# mipi_deserializer.net
KiCad netlist of a schematic drawn in Altium Designer
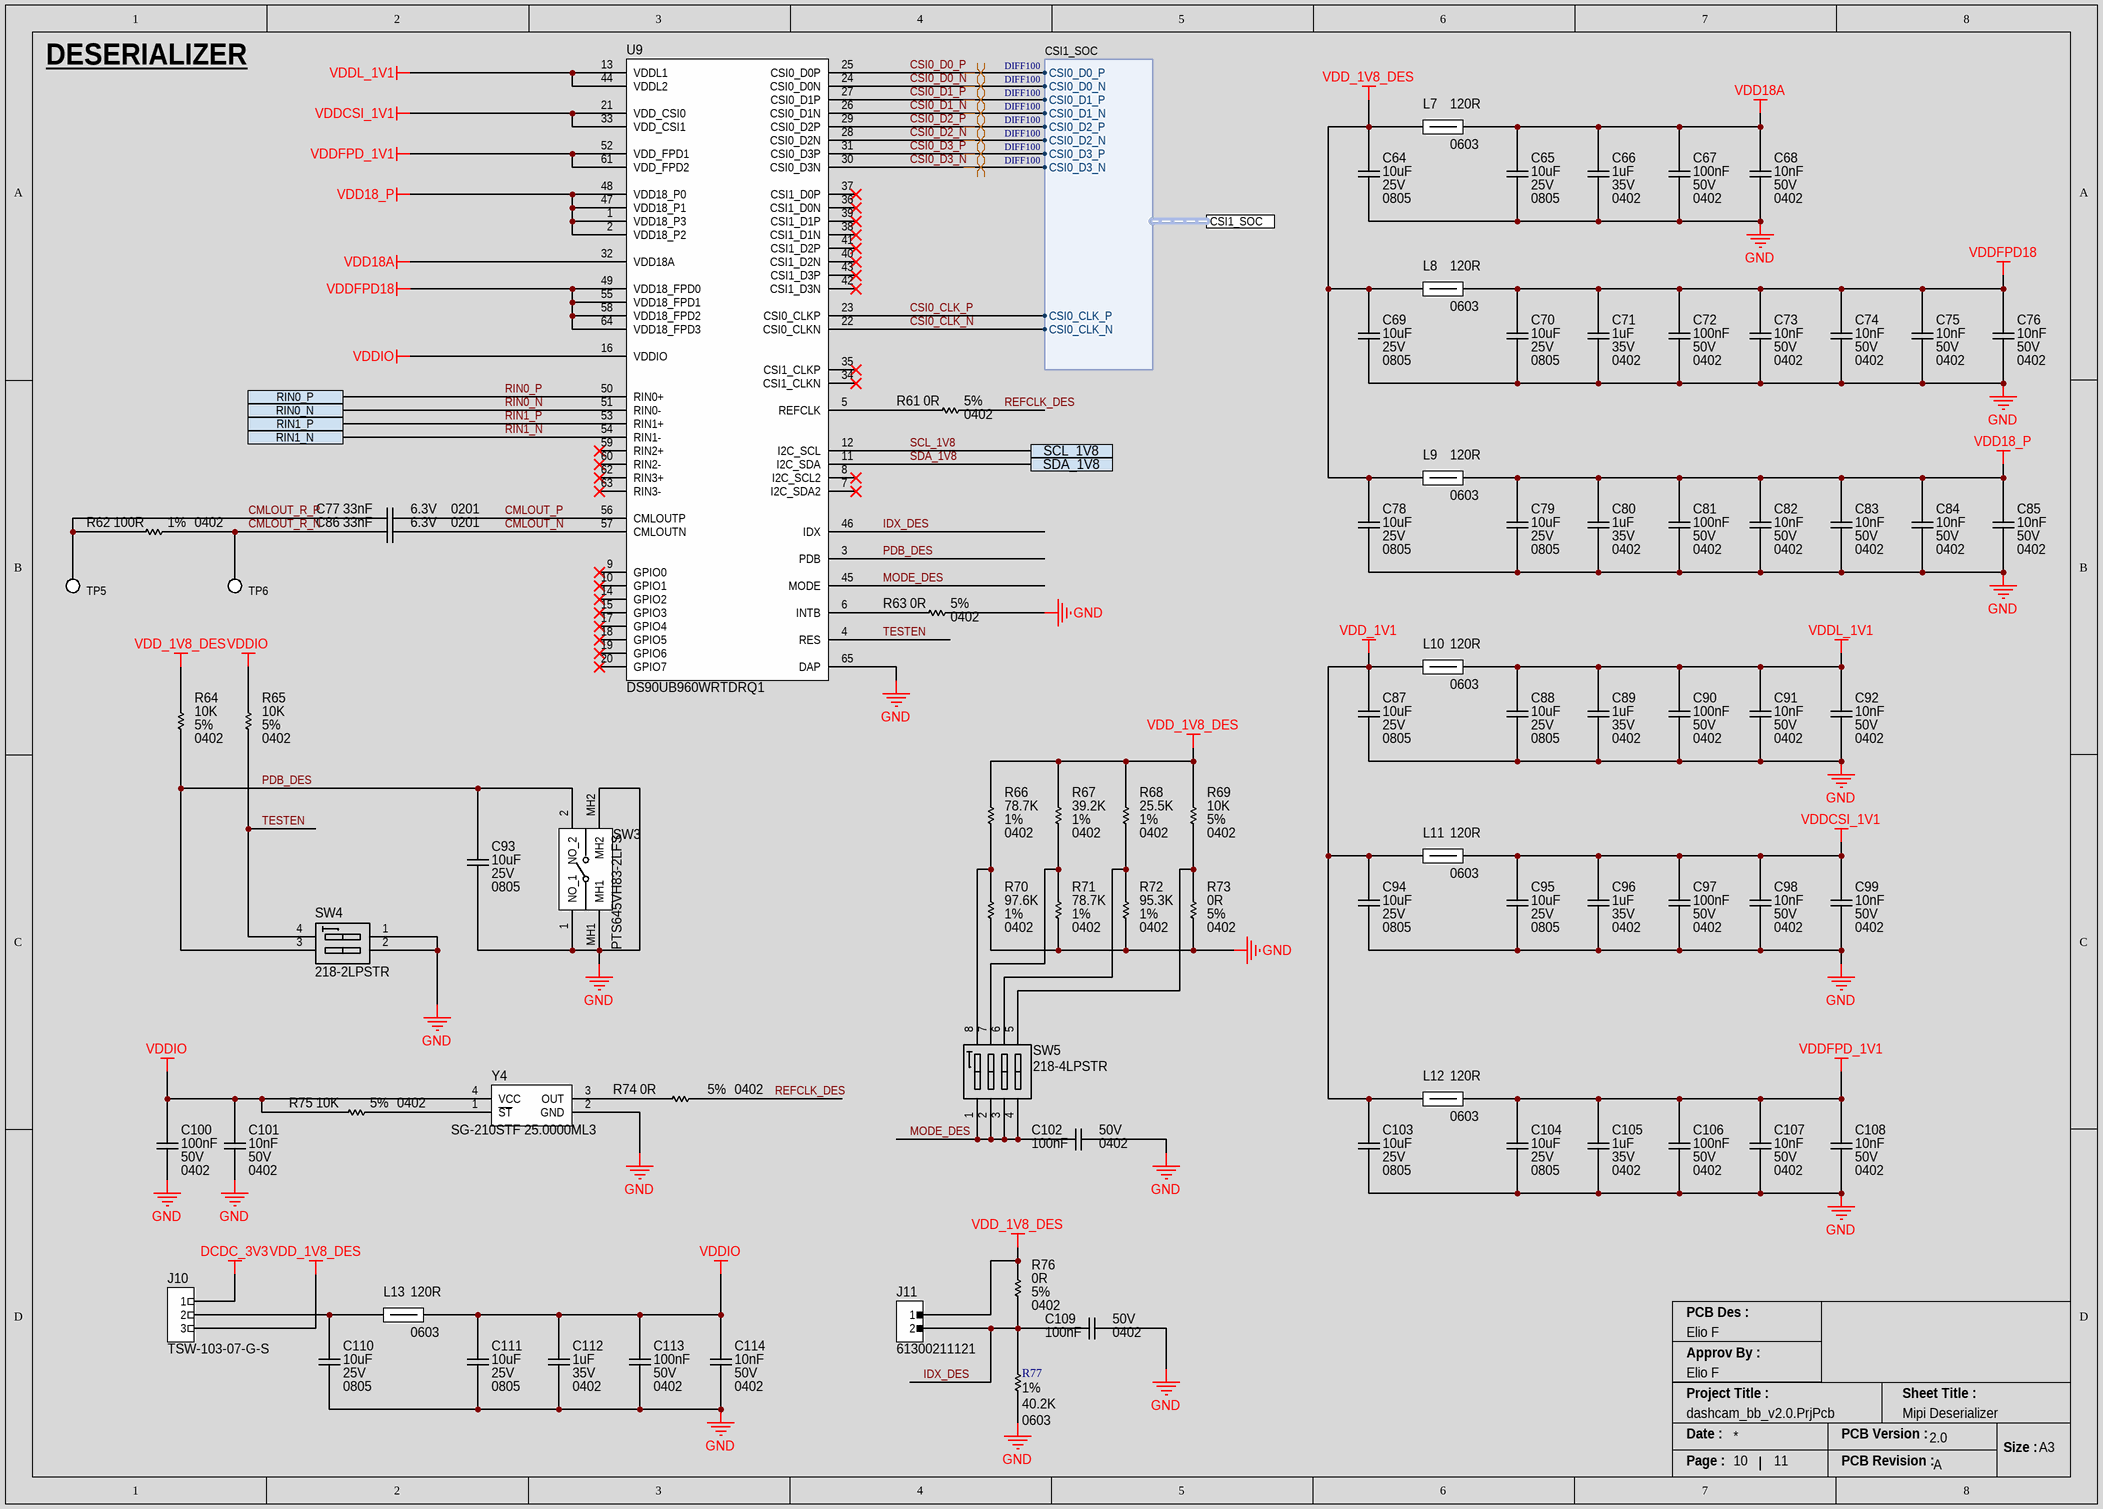
[diagram p0: mipi_deserializer.SchDoc]

(export (version "E")
  (design (tool "Eeschema 10.0.6"))
  (components
    (comp (ref "C64")
      (value "CL21A106KAYNNNE")
      (footprint "CAP_0805_CAPC2012X12N")
      (description "CAP CER 10UF 25V X5R 0805")
      (fields
        (field (name "MANUFACTURER") "Samsung")
        (field (name "TOLERANCE") "10%")
        (field (name "VOLTAGE RATING") "25V")
        (field (name "CAPACITANCE") "10uF")
        (field (name "CASE/PACKAGE") "0805")
      )
      (libsource (lib "Electronic Devices_LIB") (part "CAP_10UF_25V_X5R_0805"))
    )
    (comp (ref "C65")
      (value "CL21A106KAYNNNE")
      (footprint "CAP_0805_CAPC2012X12N")
      (description "CAP CER 10UF 25V X5R 0805")
      (fields
        (field (name "MANUFACTURER") "Samsung")
        (field (name "TOLERANCE") "10%")
        (field (name "VOLTAGE RATING") "25V")
        (field (name "CAPACITANCE") "10uF")
        (field (name "CASE/PACKAGE") "0805")
      )
      (libsource (lib "Electronic Devices_LIB") (part "CAP_10UF_25V_X5R_0805"))
    )
    (comp (ref "C66")
      (value "C1005JB1V105K050BC")
      (footprint "CAP_0402_CAPC1005X05N")
      (description "Cap Ceramic 1uF 35V JB 10% SMD 0402 85°C Punched Paper T/R")
      (fields
        (field (name "MANUFACTURER") "TDK")
        (field (name "TOLERANCE") "10%")
        (field (name "VOLTAGE RATING") "35V")
        (field (name "CAPACITANCE") "1uF")
        (field (name "CASE/PACKAGE") "0402")
      )
      (libsource (lib "Electronic Devices_LIB") (part "CAP_1uF_35V_JB_0402"))
    )
    (comp (ref "C67")
      (value "GRM155R71H104KE14D")
      (footprint "CAP_0402_CAPC1005X05N")
      (description "Multilayer Ceramic Capacitor, 0.1 uF, 16 V, ± 10%, X7R, 0402 [1005 Metric]")
      (fields
        (field (name "MANUFACTURER") "Murata")
        (field (name "TOLERANCE") "10%")
        (field (name "VOLTAGE RATING") "50V")
        (field (name "CAPACITANCE") "100nF")
        (field (name "CASE/PACKAGE") "0402")
      )
      (libsource (lib "Electronic Devices_LIB") (part "CAP_100NF_50V_X7R_0402"))
    )
    (comp (ref "C68")
      (value "GRM155R71H103KA88D")
      (footprint "CAP_0402_CAPC1005X05N")
      (description "Multilayer Ceramic Capacitors MLCC Surface Mount 0402 0.01uF 50 Volts X7R 10%")
      (fields
        (field (name "MANUFACTURER") "Murata")
        (field (name "TOLERANCE") "10%")
        (field (name "VOLTAGE RATING") "50V")
        (field (name "CAPACITANCE") "10nF")
        (field (name "CASE/PACKAGE") "0402")
      )
      (libsource (lib "Electronic Devices_LIB") (part "CAP_10nF_50V_X7R_0402"))
    )
    (comp (ref "C69")
      (value "CL21A106KAYNNNE")
      (footprint "CAP_0805_CAPC2012X12N")
      (description "CAP CER 10UF 25V X5R 0805")
      (fields
        (field (name "MANUFACTURER") "Samsung")
        (field (name "TOLERANCE") "10%")
        (field (name "VOLTAGE RATING") "25V")
        (field (name "CAPACITANCE") "10uF")
        (field (name "CASE/PACKAGE") "0805")
      )
      (libsource (lib "Electronic Devices_LIB") (part "CAP_10UF_25V_X5R_0805"))
    )
    (comp (ref "C70")
      (value "CL21A106KAYNNNE")
      (footprint "CAP_0805_CAPC2012X12N")
      (description "CAP CER 10UF 25V X5R 0805")
      (fields
        (field (name "MANUFACTURER") "Samsung")
        (field (name "TOLERANCE") "10%")
        (field (name "VOLTAGE RATING") "25V")
        (field (name "CAPACITANCE") "10uF")
        (field (name "CASE/PACKAGE") "0805")
      )
      (libsource (lib "Electronic Devices_LIB") (part "CAP_10UF_25V_X5R_0805"))
    )
    (comp (ref "C71")
      (value "C1005JB1V105K050BC")
      (footprint "CAP_0402_CAPC1005X05N")
      (description "Cap Ceramic 1uF 35V JB 10% SMD 0402 85°C Punched Paper T/R")
      (fields
        (field (name "MANUFACTURER") "TDK")
        (field (name "TOLERANCE") "10%")
        (field (name "VOLTAGE RATING") "35V")
        (field (name "CAPACITANCE") "1uF")
        (field (name "CASE/PACKAGE") "0402")
      )
      (libsource (lib "Electronic Devices_LIB") (part "CAP_1uF_35V_JB_0402"))
    )
    (comp (ref "C72")
      (value "GRM155R71H104KE14D")
      (footprint "CAP_0402_CAPC1005X05N")
      (description "Multilayer Ceramic Capacitor, 0.1 uF, 16 V, ± 10%, X7R, 0402 [1005 Metric]")
      (fields
        (field (name "MANUFACTURER") "Murata")
        (field (name "TOLERANCE") "10%")
        (field (name "VOLTAGE RATING") "50V")
        (field (name "CAPACITANCE") "100nF")
        (field (name "CASE/PACKAGE") "0402")
      )
      (libsource (lib "Electronic Devices_LIB") (part "CAP_100NF_50V_X7R_0402"))
    )
    (comp (ref "C73")
      (value "GRM155R71H103KA88D")
      (footprint "CAP_0402_CAPC1005X05N")
      (description "Multilayer Ceramic Capacitors MLCC Surface Mount 0402 0.01uF 50 Volts X7R 10%")
      (fields
        (field (name "MANUFACTURER") "Murata")
        (field (name "TOLERANCE") "10%")
        (field (name "VOLTAGE RATING") "50V")
        (field (name "CAPACITANCE") "10nF")
        (field (name "CASE/PACKAGE") "0402")
      )
      (libsource (lib "Electronic Devices_LIB") (part "CAP_10nF_50V_X7R_0402"))
    )
    (comp (ref "C74")
      (value "GRM155R71H103KA88D")
      (footprint "CAP_0402_CAPC1005X05N")
      (description "Multilayer Ceramic Capacitors MLCC Surface Mount 0402 0.01uF 50 Volts X7R 10%")
      (fields
        (field (name "MANUFACTURER") "Murata")
        (field (name "TOLERANCE") "10%")
        (field (name "VOLTAGE RATING") "50V")
        (field (name "CAPACITANCE") "10nF")
        (field (name "CASE/PACKAGE") "0402")
      )
      (libsource (lib "Electronic Devices_LIB") (part "CAP_10nF_50V_X7R_0402"))
    )
    (comp (ref "C75")
      (value "GRM155R71H103KA88D")
      (footprint "CAP_0402_CAPC1005X05N")
      (description "Multilayer Ceramic Capacitors MLCC Surface Mount 0402 0.01uF 50 Volts X7R 10%")
      (fields
        (field (name "MANUFACTURER") "Murata")
        (field (name "TOLERANCE") "10%")
        (field (name "VOLTAGE RATING") "50V")
        (field (name "CAPACITANCE") "10nF")
        (field (name "CASE/PACKAGE") "0402")
      )
      (libsource (lib "Electronic Devices_LIB") (part "CAP_10nF_50V_X7R_0402"))
    )
    (comp (ref "C76")
      (value "GRM155R71H103KA88D")
      (footprint "CAP_0402_CAPC1005X05N")
      (description "Multilayer Ceramic Capacitors MLCC Surface Mount 0402 0.01uF 50 Volts X7R 10%")
      (fields
        (field (name "MANUFACTURER") "Murata")
        (field (name "TOLERANCE") "10%")
        (field (name "VOLTAGE RATING") "50V")
        (field (name "CAPACITANCE") "10nF")
        (field (name "CASE/PACKAGE") "0402")
      )
      (libsource (lib "Electronic Devices_LIB") (part "CAP_10nF_50V_X7R_0402"))
    )
    (comp (ref "C77")
      (value "GRM033R60J333KE01D")
      (footprint "CAP_0201_CAPC0603X03N")
      (description "Multilayer Ceramic Capacitor, 0.033 uF, 6.3 V, ± 10%, X5R, 0201 [0603 Metric]")
      (fields
        (field (name "MANUFACTURER") "Murata")
        (field (name "TOLERANCE") "10%")
        (field (name "VOLTAGE RATING") "6.3V")
        (field (name "CAPACITANCE") "33nF")
        (field (name "CASE/PACKAGE") "0201")
      )
      (libsource (lib "Electronic Devices_LIB") (part "CAP_0.033uF_6.3V_X5R_0201"))
    )
    (comp (ref "C78")
      (value "CL21A106KAYNNNE")
      (footprint "CAP_0805_CAPC2012X12N")
      (description "CAP CER 10UF 25V X5R 0805")
      (fields
        (field (name "MANUFACTURER") "Samsung")
        (field (name "TOLERANCE") "10%")
        (field (name "VOLTAGE RATING") "25V")
        (field (name "CAPACITANCE") "10uF")
        (field (name "CASE/PACKAGE") "0805")
      )
      (libsource (lib "Electronic Devices_LIB") (part "CAP_10UF_25V_X5R_0805"))
    )
    (comp (ref "C79")
      (value "CL21A106KAYNNNE")
      (footprint "CAP_0805_CAPC2012X12N")
      (description "CAP CER 10UF 25V X5R 0805")
      (fields
        (field (name "MANUFACTURER") "Samsung")
        (field (name "TOLERANCE") "10%")
        (field (name "VOLTAGE RATING") "25V")
        (field (name "CAPACITANCE") "10uF")
        (field (name "CASE/PACKAGE") "0805")
      )
      (libsource (lib "Electronic Devices_LIB") (part "CAP_10UF_25V_X5R_0805"))
    )
    (comp (ref "C80")
      (value "C1005JB1V105K050BC")
      (footprint "CAP_0402_CAPC1005X05N")
      (description "Cap Ceramic 1uF 35V JB 10% SMD 0402 85°C Punched Paper T/R")
      (fields
        (field (name "MANUFACTURER") "TDK")
        (field (name "TOLERANCE") "10%")
        (field (name "VOLTAGE RATING") "35V")
        (field (name "CAPACITANCE") "1uF")
        (field (name "CASE/PACKAGE") "0402")
      )
      (libsource (lib "Electronic Devices_LIB") (part "CAP_1uF_35V_JB_0402"))
    )
    (comp (ref "C81")
      (value "GRM155R71H104KE14D")
      (footprint "CAP_0402_CAPC1005X05N")
      (description "Multilayer Ceramic Capacitor, 0.1 uF, 16 V, ± 10%, X7R, 0402 [1005 Metric]")
      (fields
        (field (name "MANUFACTURER") "Murata")
        (field (name "TOLERANCE") "10%")
        (field (name "VOLTAGE RATING") "50V")
        (field (name "CAPACITANCE") "100nF")
        (field (name "CASE/PACKAGE") "0402")
      )
      (libsource (lib "Electronic Devices_LIB") (part "CAP_100NF_50V_X7R_0402"))
    )
    (comp (ref "C82")
      (value "GRM155R71H103KA88D")
      (footprint "CAP_0402_CAPC1005X05N")
      (description "Multilayer Ceramic Capacitors MLCC Surface Mount 0402 0.01uF 50 Volts X7R 10%")
      (fields
        (field (name "MANUFACTURER") "Murata")
        (field (name "TOLERANCE") "10%")
        (field (name "VOLTAGE RATING") "50V")
        (field (name "CAPACITANCE") "10nF")
        (field (name "CASE/PACKAGE") "0402")
      )
      (libsource (lib "Electronic Devices_LIB") (part "CAP_10nF_50V_X7R_0402"))
    )
    (comp (ref "C83")
      (value "GRM155R71H103KA88D")
      (footprint "CAP_0402_CAPC1005X05N")
      (description "Multilayer Ceramic Capacitors MLCC Surface Mount 0402 0.01uF 50 Volts X7R 10%")
      (fields
        (field (name "MANUFACTURER") "Murata")
        (field (name "TOLERANCE") "10%")
        (field (name "VOLTAGE RATING") "50V")
        (field (name "CAPACITANCE") "10nF")
        (field (name "CASE/PACKAGE") "0402")
      )
      (libsource (lib "Electronic Devices_LIB") (part "CAP_10nF_50V_X7R_0402"))
    )
    (comp (ref "C84")
      (value "GRM155R71H103KA88D")
      (footprint "CAP_0402_CAPC1005X05N")
      (description "Multilayer Ceramic Capacitors MLCC Surface Mount 0402 0.01uF 50 Volts X7R 10%")
      (fields
        (field (name "MANUFACTURER") "Murata")
        (field (name "TOLERANCE") "10%")
        (field (name "VOLTAGE RATING") "50V")
        (field (name "CAPACITANCE") "10nF")
        (field (name "CASE/PACKAGE") "0402")
      )
      (libsource (lib "Electronic Devices_LIB") (part "CAP_10nF_50V_X7R_0402"))
    )
    (comp (ref "C85")
      (value "GRM155R71H103KA88D")
      (footprint "CAP_0402_CAPC1005X05N")
      (description "Multilayer Ceramic Capacitors MLCC Surface Mount 0402 0.01uF 50 Volts X7R 10%")
      (fields
        (field (name "MANUFACTURER") "Murata")
        (field (name "TOLERANCE") "10%")
        (field (name "VOLTAGE RATING") "50V")
        (field (name "CAPACITANCE") "10nF")
        (field (name "CASE/PACKAGE") "0402")
      )
      (libsource (lib "Electronic Devices_LIB") (part "CAP_10nF_50V_X7R_0402"))
    )
    (comp (ref "C86")
      (value "GRM033R60J333KE01D")
      (footprint "CAP_0201_CAPC0603X03N")
      (description "Multilayer Ceramic Capacitor, 0.033 uF, 6.3 V, ± 10%, X5R, 0201 [0603 Metric]")
      (fields
        (field (name "MANUFACTURER") "Murata")
        (field (name "TOLERANCE") "10%")
        (field (name "VOLTAGE RATING") "6.3V")
        (field (name "CAPACITANCE") "33nF")
        (field (name "CASE/PACKAGE") "0201")
      )
      (libsource (lib "Electronic Devices_LIB") (part "CAP_0.033uF_6.3V_X5R_0201"))
    )
    (comp (ref "C87")
      (value "CL21A106KAYNNNE")
      (footprint "CAP_0805_CAPC2012X12N")
      (description "CAP CER 10UF 25V X5R 0805")
      (fields
        (field (name "MANUFACTURER") "Samsung")
        (field (name "TOLERANCE") "10%")
        (field (name "VOLTAGE RATING") "25V")
        (field (name "CAPACITANCE") "10uF")
        (field (name "CASE/PACKAGE") "0805")
      )
      (libsource (lib "Electronic Devices_LIB") (part "CAP_10UF_25V_X5R_0805"))
    )
    (comp (ref "C88")
      (value "CL21A106KAYNNNE")
      (footprint "CAP_0805_CAPC2012X12N")
      (description "CAP CER 10UF 25V X5R 0805")
      (fields
        (field (name "MANUFACTURER") "Samsung")
        (field (name "TOLERANCE") "10%")
        (field (name "VOLTAGE RATING") "25V")
        (field (name "CAPACITANCE") "10uF")
        (field (name "CASE/PACKAGE") "0805")
      )
      (libsource (lib "Electronic Devices_LIB") (part "CAP_10UF_25V_X5R_0805"))
    )
    (comp (ref "C89")
      (value "C1005JB1V105K050BC")
      (footprint "CAP_0402_CAPC1005X05N")
      (description "Cap Ceramic 1uF 35V JB 10% SMD 0402 85°C Punched Paper T/R")
      (fields
        (field (name "MANUFACTURER") "TDK")
        (field (name "TOLERANCE") "10%")
        (field (name "VOLTAGE RATING") "35V")
        (field (name "CAPACITANCE") "1uF")
        (field (name "CASE/PACKAGE") "0402")
      )
      (libsource (lib "Electronic Devices_LIB") (part "CAP_1uF_35V_JB_0402"))
    )
    (comp (ref "C90")
      (value "GRM155R71H104KE14D")
      (footprint "CAP_0402_CAPC1005X05N")
      (description "Multilayer Ceramic Capacitor, 0.1 uF, 16 V, ± 10%, X7R, 0402 [1005 Metric]")
      (fields
        (field (name "MANUFACTURER") "Murata")
        (field (name "TOLERANCE") "10%")
        (field (name "VOLTAGE RATING") "50V")
        (field (name "CAPACITANCE") "100nF")
        (field (name "CASE/PACKAGE") "0402")
      )
      (libsource (lib "Electronic Devices_LIB") (part "CAP_100NF_50V_X7R_0402"))
    )
    (comp (ref "C91")
      (value "GRM155R71H103KA88D")
      (footprint "CAP_0402_CAPC1005X05N")
      (description "Multilayer Ceramic Capacitors MLCC Surface Mount 0402 0.01uF 50 Volts X7R 10%")
      (fields
        (field (name "MANUFACTURER") "Murata")
        (field (name "TOLERANCE") "10%")
        (field (name "VOLTAGE RATING") "50V")
        (field (name "CAPACITANCE") "10nF")
        (field (name "CASE/PACKAGE") "0402")
      )
      (libsource (lib "Electronic Devices_LIB") (part "CAP_10nF_50V_X7R_0402"))
    )
    (comp (ref "C92")
      (value "GRM155R71H103KA88D")
      (footprint "CAP_0402_CAPC1005X05N")
      (description "Multilayer Ceramic Capacitors MLCC Surface Mount 0402 0.01uF 50 Volts X7R 10%")
      (fields
        (field (name "MANUFACTURER") "Murata")
        (field (name "TOLERANCE") "10%")
        (field (name "VOLTAGE RATING") "50V")
        (field (name "CAPACITANCE") "10nF")
        (field (name "CASE/PACKAGE") "0402")
      )
      (libsource (lib "Electronic Devices_LIB") (part "CAP_10nF_50V_X7R_0402"))
    )
    (comp (ref "C93")
      (value "CL21A106KAYNNNE")
      (footprint "CAP_0805_CAPC2012X12N")
      (description "CAP CER 10UF 25V X5R 0805")
      (fields
        (field (name "MANUFACTURER") "Samsung")
        (field (name "TOLERANCE") "10%")
        (field (name "VOLTAGE RATING") "25V")
        (field (name "CAPACITANCE") "10uF")
        (field (name "CASE/PACKAGE") "0805")
      )
      (libsource (lib "Electronic Devices_LIB") (part "CAP_10UF_25V_X5R_0805"))
    )
    (comp (ref "C94")
      (value "CL21A106KAYNNNE")
      (footprint "CAP_0805_CAPC2012X12N")
      (description "CAP CER 10UF 25V X5R 0805")
      (fields
        (field (name "MANUFACTURER") "Samsung")
        (field (name "TOLERANCE") "10%")
        (field (name "VOLTAGE RATING") "25V")
        (field (name "CAPACITANCE") "10uF")
        (field (name "CASE/PACKAGE") "0805")
      )
      (libsource (lib "Electronic Devices_LIB") (part "CAP_10UF_25V_X5R_0805"))
    )
    (comp (ref "C95")
      (value "CL21A106KAYNNNE")
      (footprint "CAP_0805_CAPC2012X12N")
      (description "CAP CER 10UF 25V X5R 0805")
      (fields
        (field (name "MANUFACTURER") "Samsung")
        (field (name "TOLERANCE") "10%")
        (field (name "VOLTAGE RATING") "25V")
        (field (name "CAPACITANCE") "10uF")
        (field (name "CASE/PACKAGE") "0805")
      )
      (libsource (lib "Electronic Devices_LIB") (part "CAP_10UF_25V_X5R_0805"))
    )
    (comp (ref "C96")
      (value "C1005JB1V105K050BC")
      (footprint "CAP_0402_CAPC1005X05N")
      (description "Cap Ceramic 1uF 35V JB 10% SMD 0402 85°C Punched Paper T/R")
      (fields
        (field (name "MANUFACTURER") "TDK")
        (field (name "TOLERANCE") "10%")
        (field (name "VOLTAGE RATING") "35V")
        (field (name "CAPACITANCE") "1uF")
        (field (name "CASE/PACKAGE") "0402")
      )
      (libsource (lib "Electronic Devices_LIB") (part "CAP_1uF_35V_JB_0402"))
    )
    (comp (ref "C97")
      (value "GRM155R71H104KE14D")
      (footprint "CAP_0402_CAPC1005X05N")
      (description "Multilayer Ceramic Capacitor, 0.1 uF, 16 V, ± 10%, X7R, 0402 [1005 Metric]")
      (fields
        (field (name "MANUFACTURER") "Murata")
        (field (name "TOLERANCE") "10%")
        (field (name "VOLTAGE RATING") "50V")
        (field (name "CAPACITANCE") "100nF")
        (field (name "CASE/PACKAGE") "0402")
      )
      (libsource (lib "Electronic Devices_LIB") (part "CAP_100NF_50V_X7R_0402"))
    )
    (comp (ref "C98")
      (value "GRM155R71H103KA88D")
      (footprint "CAP_0402_CAPC1005X05N")
      (description "Multilayer Ceramic Capacitors MLCC Surface Mount 0402 0.01uF 50 Volts X7R 10%")
      (fields
        (field (name "MANUFACTURER") "Murata")
        (field (name "TOLERANCE") "10%")
        (field (name "VOLTAGE RATING") "50V")
        (field (name "CAPACITANCE") "10nF")
        (field (name "CASE/PACKAGE") "0402")
      )
      (libsource (lib "Electronic Devices_LIB") (part "CAP_10nF_50V_X7R_0402"))
    )
    (comp (ref "C99")
      (value "GRM155R71H103KA88D")
      (footprint "CAP_0402_CAPC1005X05N")
      (description "Multilayer Ceramic Capacitors MLCC Surface Mount 0402 0.01uF 50 Volts X7R 10%")
      (fields
        (field (name "MANUFACTURER") "Murata")
        (field (name "TOLERANCE") "10%")
        (field (name "VOLTAGE RATING") "50V")
        (field (name "CAPACITANCE") "10nF")
        (field (name "CASE/PACKAGE") "0402")
      )
      (libsource (lib "Electronic Devices_LIB") (part "CAP_10nF_50V_X7R_0402"))
    )
    (comp (ref "C100")
      (value "GRM155R71H104KE14D")
      (footprint "CAP_0402_CAPC1005X05N")
      (description "Multilayer Ceramic Capacitor, 0.1 uF, 16 V, ± 10%, X7R, 0402 [1005 Metric]")
      (fields
        (field (name "MANUFACTURER") "Murata")
        (field (name "TOLERANCE") "10%")
        (field (name "VOLTAGE RATING") "50V")
        (field (name "CAPACITANCE") "100nF")
        (field (name "CASE/PACKAGE") "0402")
      )
      (libsource (lib "Electronic Devices_LIB") (part "CAP_100NF_50V_X7R_0402"))
    )
    (comp (ref "C101")
      (value "GRM155R71H103KA88D")
      (footprint "CAP_0402_CAPC1005X05N")
      (description "Multilayer Ceramic Capacitors MLCC Surface Mount 0402 0.01uF 50 Volts X7R 10%")
      (fields
        (field (name "MANUFACTURER") "Murata")
        (field (name "TOLERANCE") "10%")
        (field (name "VOLTAGE RATING") "50V")
        (field (name "CAPACITANCE") "10nF")
        (field (name "CASE/PACKAGE") "0402")
      )
      (libsource (lib "Electronic Devices_LIB") (part "CAP_10nF_50V_X7R_0402"))
    )
    (comp (ref "C102")
      (value "GRM155R71H104KE14D")
      (footprint "CAP_0402_CAPC1005X05N")
      (description "Multilayer Ceramic Capacitor, 0.1 uF, 16 V, ± 10%, X7R, 0402 [1005 Metric]")
      (fields
        (field (name "MANUFACTURER") "Murata")
        (field (name "TOLERANCE") "10%")
        (field (name "VOLTAGE RATING") "50V")
        (field (name "CAPACITANCE") "100nF")
        (field (name "CASE/PACKAGE") "0402")
      )
      (libsource (lib "Electronic Devices_LIB") (part "CAP_100NF_50V_X7R_0402"))
    )
    (comp (ref "C103")
      (value "CL21A106KAYNNNE")
      (footprint "CAP_0805_CAPC2012X12N")
      (description "CAP CER 10UF 25V X5R 0805")
      (fields
        (field (name "MANUFACTURER") "Samsung")
        (field (name "TOLERANCE") "10%")
        (field (name "VOLTAGE RATING") "25V")
        (field (name "CAPACITANCE") "10uF")
        (field (name "CASE/PACKAGE") "0805")
      )
      (libsource (lib "Electronic Devices_LIB") (part "CAP_10UF_25V_X5R_0805"))
    )
    (comp (ref "C104")
      (value "CL21A106KAYNNNE")
      (footprint "CAP_0805_CAPC2012X12N")
      (description "CAP CER 10UF 25V X5R 0805")
      (fields
        (field (name "MANUFACTURER") "Samsung")
        (field (name "TOLERANCE") "10%")
        (field (name "VOLTAGE RATING") "25V")
        (field (name "CAPACITANCE") "10uF")
        (field (name "CASE/PACKAGE") "0805")
      )
      (libsource (lib "Electronic Devices_LIB") (part "CAP_10UF_25V_X5R_0805"))
    )
    (comp (ref "C105")
      (value "C1005JB1V105K050BC")
      (footprint "CAP_0402_CAPC1005X05N")
      (description "Cap Ceramic 1uF 35V JB 10% SMD 0402 85°C Punched Paper T/R")
      (fields
        (field (name "MANUFACTURER") "TDK")
        (field (name "TOLERANCE") "10%")
        (field (name "VOLTAGE RATING") "35V")
        (field (name "CAPACITANCE") "1uF")
        (field (name "CASE/PACKAGE") "0402")
      )
      (libsource (lib "Electronic Devices_LIB") (part "CAP_1uF_35V_JB_0402"))
    )
    (comp (ref "C106")
      (value "GRM155R71H104KE14D")
      (footprint "CAP_0402_CAPC1005X05N")
      (description "Multilayer Ceramic Capacitor, 0.1 uF, 16 V, ± 10%, X7R, 0402 [1005 Metric]")
      (fields
        (field (name "MANUFACTURER") "Murata")
        (field (name "TOLERANCE") "10%")
        (field (name "VOLTAGE RATING") "50V")
        (field (name "CAPACITANCE") "100nF")
        (field (name "CASE/PACKAGE") "0402")
      )
      (libsource (lib "Electronic Devices_LIB") (part "CAP_100NF_50V_X7R_0402"))
    )
    (comp (ref "C107")
      (value "GRM155R71H103KA88D")
      (footprint "CAP_0402_CAPC1005X05N")
      (description "Multilayer Ceramic Capacitors MLCC Surface Mount 0402 0.01uF 50 Volts X7R 10%")
      (fields
        (field (name "MANUFACTURER") "Murata")
        (field (name "TOLERANCE") "10%")
        (field (name "VOLTAGE RATING") "50V")
        (field (name "CAPACITANCE") "10nF")
        (field (name "CASE/PACKAGE") "0402")
      )
      (libsource (lib "Electronic Devices_LIB") (part "CAP_10nF_50V_X7R_0402"))
    )
    (comp (ref "C108")
      (value "GRM155R71H103KA88D")
      (footprint "CAP_0402_CAPC1005X05N")
      (description "Multilayer Ceramic Capacitors MLCC Surface Mount 0402 0.01uF 50 Volts X7R 10%")
      (fields
        (field (name "MANUFACTURER") "Murata")
        (field (name "TOLERANCE") "10%")
        (field (name "VOLTAGE RATING") "50V")
        (field (name "CAPACITANCE") "10nF")
        (field (name "CASE/PACKAGE") "0402")
      )
      (libsource (lib "Electronic Devices_LIB") (part "CAP_10nF_50V_X7R_0402"))
    )
    (comp (ref "C109")
      (value "GRM155R71H104KE14D")
      (footprint "CAP_0402_CAPC1005X05N")
      (description "Multilayer Ceramic Capacitor, 0.1 uF, 16 V, ± 10%, X7R, 0402 [1005 Metric]")
      (fields
        (field (name "MANUFACTURER") "Murata")
        (field (name "TOLERANCE") "10%")
        (field (name "VOLTAGE RATING") "50V")
        (field (name "CAPACITANCE") "100nF")
        (field (name "CASE/PACKAGE") "0402")
      )
      (libsource (lib "Electronic Devices_LIB") (part "CAP_100NF_50V_X7R_0402"))
    )
    (comp (ref "C110")
      (value "CL21A106KAYNNNE")
      (footprint "CAP_0805_CAPC2012X12N")
      (description "CAP CER 10UF 25V X5R 0805")
      (fields
        (field (name "MANUFACTURER") "Samsung")
        (field (name "TOLERANCE") "10%")
        (field (name "VOLTAGE RATING") "25V")
        (field (name "CAPACITANCE") "10uF")
        (field (name "CASE/PACKAGE") "0805")
      )
      (libsource (lib "Electronic Devices_LIB") (part "CAP_10UF_25V_X5R_0805"))
    )
    (comp (ref "C111")
      (value "CL21A106KAYNNNE")
      (footprint "CAP_0805_CAPC2012X12N")
      (description "CAP CER 10UF 25V X5R 0805")
      (fields
        (field (name "MANUFACTURER") "Samsung")
        (field (name "TOLERANCE") "10%")
        (field (name "VOLTAGE RATING") "25V")
        (field (name "CAPACITANCE") "10uF")
        (field (name "CASE/PACKAGE") "0805")
      )
      (libsource (lib "Electronic Devices_LIB") (part "CAP_10UF_25V_X5R_0805"))
    )
    (comp (ref "C112")
      (value "C1005JB1V105K050BC")
      (footprint "CAP_0402_CAPC1005X05N")
      (description "Cap Ceramic 1uF 35V JB 10% SMD 0402 85°C Punched Paper T/R")
      (fields
        (field (name "MANUFACTURER") "TDK")
        (field (name "TOLERANCE") "10%")
        (field (name "VOLTAGE RATING") "35V")
        (field (name "CAPACITANCE") "1uF")
        (field (name "CASE/PACKAGE") "0402")
      )
      (libsource (lib "Electronic Devices_LIB") (part "CAP_1uF_35V_JB_0402"))
    )
    (comp (ref "C113")
      (value "GRM155R71H104KE14D")
      (footprint "CAP_0402_CAPC1005X05N")
      (description "Multilayer Ceramic Capacitor, 0.1 uF, 16 V, ± 10%, X7R, 0402 [1005 Metric]")
      (fields
        (field (name "MANUFACTURER") "Murata")
        (field (name "TOLERANCE") "10%")
        (field (name "VOLTAGE RATING") "50V")
        (field (name "CAPACITANCE") "100nF")
        (field (name "CASE/PACKAGE") "0402")
      )
      (libsource (lib "Electronic Devices_LIB") (part "CAP_100NF_50V_X7R_0402"))
    )
    (comp (ref "C114")
      (value "GRM155R71H103KA88D")
      (footprint "CAP_0402_CAPC1005X05N")
      (description "Multilayer Ceramic Capacitors MLCC Surface Mount 0402 0.01uF 50 Volts X7R 10%")
      (fields
        (field (name "MANUFACTURER") "Murata")
        (field (name "TOLERANCE") "10%")
        (field (name "VOLTAGE RATING") "50V")
        (field (name "CAPACITANCE") "10nF")
        (field (name "CASE/PACKAGE") "0402")
      )
      (libsource (lib "Electronic Devices_LIB") (part "CAP_10nF_50V_X7R_0402"))
    )
    (comp (ref "J10")
      (value "TSW-103-07-G-S")
      (footprint "CONN_HEADER_MALE_SAMTEC_TSW-103-07-G-S")
      (description "Conn Unshrouded Header HDR 3 POS 2.54mm Solder ST Top Entry Thru-Hole Bulk")
      (fields (field (name "MANUFACTURER") "Samtec"))
      (libsource (lib "Electronic Devices_LIB") (part "CONN_HEADER_MALE_3P_2.54mm_TSW-103-07-G-S"))
    )
    (comp (ref "J11")
      (value "61300211121")
      (footprint "HEADER_MALE_HDRV2W110P0X254_1X2_508X254X854P")
      (description "THT Vertical Pin Header WR-PHD, Pitch 2.54 mm, Single Row, 2 pins")
      (fields (field (name "MANUFACTURER") "Wurth Electronics"))
      (libsource (lib "Electronic Devices_LIB") (part "CONN_HEADER_MALE_2P_2.54_61300211121"))
    )
    (comp (ref "L7")
      (value "BLM18PG121SH1D")
      (footprint "IND_0603_INDC1608X08N")
      (description "Ferrite Beads Multi-Layer 120Ohm 25% 100MHz 2A 50mOhm DCR 0603 Automotive Paper T/R")
      (fields
        (field (name "MANUFACTURER") "Murata")
        (field (name "TOLERANCE") "25%")
        (field (name "IMPEDANCE") "120R")
        (field (name "CASE/PACKAGE") "0603")
      )
      (libsource (lib "Electronic Devices_LIB") (part "IND_FERRITE_BEADS_120R_2A_0603_BLM18PG121SH1D"))
    )
    (comp (ref "L8")
      (value "BLM18PG121SH1D")
      (footprint "IND_0603_INDC1608X08N")
      (description "Ferrite Beads Multi-Layer 120Ohm 25% 100MHz 2A 50mOhm DCR 0603 Automotive Paper T/R")
      (fields
        (field (name "MANUFACTURER") "Murata")
        (field (name "TOLERANCE") "25%")
        (field (name "IMPEDANCE") "120R")
        (field (name "CASE/PACKAGE") "0603")
      )
      (libsource (lib "Electronic Devices_LIB") (part "IND_FERRITE_BEADS_120R_2A_0603_BLM18PG121SH1D"))
    )
    (comp (ref "L9")
      (value "BLM18PG121SH1D")
      (footprint "IND_0603_INDC1608X08N")
      (description "Ferrite Beads Multi-Layer 120Ohm 25% 100MHz 2A 50mOhm DCR 0603 Automotive Paper T/R")
      (fields
        (field (name "MANUFACTURER") "Murata")
        (field (name "TOLERANCE") "25%")
        (field (name "IMPEDANCE") "120R")
        (field (name "CASE/PACKAGE") "0603")
      )
      (libsource (lib "Electronic Devices_LIB") (part "IND_FERRITE_BEADS_120R_2A_0603_BLM18PG121SH1D"))
    )
    (comp (ref "L10")
      (value "BLM18PG121SH1D")
      (footprint "IND_0603_INDC1608X08N")
      (description "Ferrite Beads Multi-Layer 120Ohm 25% 100MHz 2A 50mOhm DCR 0603 Automotive Paper T/R")
      (fields
        (field (name "MANUFACTURER") "Murata")
        (field (name "TOLERANCE") "25%")
        (field (name "IMPEDANCE") "120R")
        (field (name "CASE/PACKAGE") "0603")
      )
      (libsource (lib "Electronic Devices_LIB") (part "IND_FERRITE_BEADS_120R_2A_0603_BLM18PG121SH1D"))
    )
    (comp (ref "L11")
      (value "BLM18PG121SH1D")
      (footprint "IND_0603_INDC1608X08N")
      (description "Ferrite Beads Multi-Layer 120Ohm 25% 100MHz 2A 50mOhm DCR 0603 Automotive Paper T/R")
      (fields
        (field (name "MANUFACTURER") "Murata")
        (field (name "TOLERANCE") "25%")
        (field (name "IMPEDANCE") "120R")
        (field (name "CASE/PACKAGE") "0603")
      )
      (libsource (lib "Electronic Devices_LIB") (part "IND_FERRITE_BEADS_120R_2A_0603_BLM18PG121SH1D"))
    )
    (comp (ref "L12")
      (value "BLM18PG121SH1D")
      (footprint "IND_0603_INDC1608X08N")
      (description "Ferrite Beads Multi-Layer 120Ohm 25% 100MHz 2A 50mOhm DCR 0603 Automotive Paper T/R")
      (fields
        (field (name "MANUFACTURER") "Murata")
        (field (name "TOLERANCE") "25%")
        (field (name "IMPEDANCE") "120R")
        (field (name "CASE/PACKAGE") "0603")
      )
      (libsource (lib "Electronic Devices_LIB") (part "IND_FERRITE_BEADS_120R_2A_0603_BLM18PG121SH1D"))
    )
    (comp (ref "L13")
      (value "BLM18PG121SH1D")
      (footprint "IND_0603_INDC1608X08N")
      (description "Ferrite Beads Multi-Layer 120Ohm 25% 100MHz 2A 50mOhm DCR 0603 Automotive Paper T/R")
      (fields
        (field (name "MANUFACTURER") "Murata")
        (field (name "TOLERANCE") "25%")
        (field (name "IMPEDANCE") "120R")
        (field (name "CASE/PACKAGE") "0603")
      )
      (libsource (lib "Electronic Devices_LIB") (part "IND_FERRITE_BEADS_120R_2A_0603_BLM18PG121SH1D"))
    )
    (comp (ref "R61")
      (value "ERJ-2GE0R00X")
      (footprint "RES_0402_RESC1005X04N")
      (description "SMD Chip Resistor, Jumper, 0 ohm, 100 mW, 0402 [1005 Metric], Thick Film, General Purpose")
      (fields
        (field (name "MANUFACTURER") "Panasonic")
        (field (name "CASE CODE (IMPERIAL)") "0402")
        (field (name "TOLERANCE") "5%")
        (field (name "RESISTANCE") "0R")
      )
      (libsource (lib "Electronic Devices_LIB") (part "RES_0R_5%_100mW_0402"))
    )
    (comp (ref "R62")
      (value "ERJ-2RKF1000X")
      (footprint "RES_0402_RESC1005X04N")
      (description "Resistor Thick Film 0402 100 Ohm 1% 1/10W 100ppm/C Molded SMD Punched Carrier T/R")
      (fields
        (field (name "MANUFACTURER") "Panasonic")
        (field (name "TOLERANCE") "1%")
        (field (name "RESISTANCE") "100R")
        (field (name "CASE/PACKAGE") "0402")
      )
      (libsource (lib "Electronic Devices_LIB") (part "RES_100R_1%_100mW_0402"))
    )
    (comp (ref "R63")
      (value "ERJ-2GE0R00X")
      (footprint "RES_0402_RESC1005X04N")
      (description "SMD Chip Resistor, Jumper, 0 ohm, 100 mW, 0402 [1005 Metric], Thick Film, General Purpose")
      (fields
        (field (name "MANUFACTURER") "Panasonic")
        (field (name "CASE CODE (IMPERIAL)") "0402")
        (field (name "TOLERANCE") "5%")
        (field (name "RESISTANCE") "0R")
      )
      (libsource (lib "Electronic Devices_LIB") (part "RES_0R_5%_100mW_0402"))
    )
    (comp (ref "R64")
      (value "ERJ-2GEJ103X")
      (footprint "RES_0402_RESC1005X04N")
      (description "Res Thick Film 0402 10K Ohm 5% 1/10W ±200ppm/°C Molded SMD Punched Carrier T/R")
      (fields
        (field (name "MANUFACTURER") "Panasonic")
        (field (name "TOLERANCE") "5%")
        (field (name "RESISTANCE") "10K")
        (field (name "CASE/PACKAGE") "0402")
      )
      (libsource (lib "Electronic Devices_LIB") (part "RES_10K_5%_100mW_0402"))
    )
    (comp (ref "R65")
      (value "ERJ-2GEJ103X")
      (footprint "RES_0402_RESC1005X04N")
      (description "Res Thick Film 0402 10K Ohm 5% 1/10W ±200ppm/°C Molded SMD Punched Carrier T/R")
      (fields
        (field (name "MANUFACTURER") "Panasonic")
        (field (name "TOLERANCE") "5%")
        (field (name "RESISTANCE") "10K")
        (field (name "CASE/PACKAGE") "0402")
      )
      (libsource (lib "Electronic Devices_LIB") (part "RES_10K_5%_100mW_0402"))
    )
    (comp (ref "R66")
      (value "CRCW040278K7FKED")
      (footprint "RES_0402_RESC1005X04N")
      (description "Res Thick Film 0402 78.7K Ohm 1% 1/16W ±100ppm/°C Molded SMD Paper T/R")
      (fields
        (field (name "MANUFACTURER") "Vishay")
        (field (name "TOLERANCE") "1%")
        (field (name "RESISTANCE") "78.7K")
        (field (name "RESISTANCE TOLERANCE") "1%")
        (field (name "CASE CODE (IMPERIAL)") "0402")
      )
      (libsource (lib "Electronic Devices_LIB") (part "RES_78.7K_1%_63mW_0402"))
    )
    (comp (ref "R67")
      (value "CRCW040239K2FKED")
      (footprint "RES_0402_RESC1005X04N")
      (description "Res Thick Film 0402 39.2K Ohm 1% 1/16W ±100ppm/°C Molded SMD SMD Paper T/R")
      (fields
        (field (name "MANUFACTURER") "Vishay")
        (field (name "RESISTANCE") "39.2K")
        (field (name "TOLERANCE") "1%")
        (field (name "CASE CODE (IMPERIAL)") "0402")
      )
      (libsource (lib "Electronic Devices_LIB") (part "RES_39.2K_1%_63mW_0402"))
    )
    (comp (ref "R68")
      (value "CRCW040225K5FKED")
      (footprint "RES_0402_RESC1005X04N")
      (description "Res Thick Film 0402 25.5K Ohm 1% 1/16W ±100ppm/°C Molded SMD SMD Paper T/R")
      (fields
        (field (name "MANUFACTURER") "Vishay")
        (field (name "CASE CODE (IMPERIAL)") "0402")
        (field (name "TOLERANCE") "1%")
        (field (name "RESISTANCE") "25.5K")
      )
      (libsource (lib "Electronic Devices_LIB") (part "RES_25.5K_1%_63mW_0402"))
    )
    (comp (ref "R69")
      (value "ERJ-2GEJ103X")
      (footprint "RES_0402_RESC1005X04N")
      (description "Res Thick Film 0402 10K Ohm 5% 1/10W ±200ppm/°C Molded SMD Punched Carrier T/R")
      (fields
        (field (name "MANUFACTURER") "Panasonic")
        (field (name "TOLERANCE") "5%")
        (field (name "RESISTANCE") "10K")
        (field (name "CASE/PACKAGE") "0402")
      )
      (libsource (lib "Electronic Devices_LIB") (part "RES_10K_5%_100mW_0402"))
    )
    (comp (ref "R70")
      (value "CRCW040297K6FKED")
      (footprint "RES_0402_RESC1005X04N")
      (description "CRCW Series 0402 97.6 kOhm 0.063 W ±1 % ±100 ppm/K SMT Thick Film Chip Resistor")
      (fields
        (field (name "MANUFACTURER") "Vishay")
        (field (name "RESISTANCE") "97.6K")
        (field (name "TOLERANCE") "1%")
        (field (name "CASE/PACKAGE") "0402")
      )
      (libsource (lib "Electronic Devices_LIB") (part "RES_97.6K_1%_63mW_0402"))
    )
    (comp (ref "R71")
      (value "CRCW040278K7FKED")
      (footprint "RES_0402_RESC1005X04N")
      (description "Res Thick Film 0402 78.7K Ohm 1% 1/16W ±100ppm/°C Molded SMD Paper T/R")
      (fields
        (field (name "MANUFACTURER") "Vishay")
        (field (name "TOLERANCE") "1%")
        (field (name "RESISTANCE") "78.7K")
        (field (name "RESISTANCE TOLERANCE") "1%")
        (field (name "CASE CODE (IMPERIAL)") "0402")
      )
      (libsource (lib "Electronic Devices_LIB") (part "RES_78.7K_1%_63mW_0402"))
    )
    (comp (ref "R72")
      (value "CRCW040295K3FKED")
      (footprint "RES_0402_RESC1005X04N")
      (description "CRCW FIXED RESISTOR 0402 (1005Metric) Chip Resistor ±1% ±100ppm/C 95.3kOhm 0.063W 1/16W")
      (fields
        (field (name "MANUFACTURER") "Vishay")
        (field (name "SIZE CODE") "0402")
        (field (name "RESISTANCE") "95.3K")
        (field (name "TOLERANCE") "1%")
      )
      (libsource (lib "Electronic Devices_LIB") (part "RES_95.3K_1%_63mW_0402"))
    )
    (comp (ref "R73")
      (value "ERJ-2GE0R00X")
      (footprint "RES_0402_RESC1005X04N")
      (description "SMD Chip Resistor, Jumper, 0 ohm, 100 mW, 0402 [1005 Metric], Thick Film, General Purpose")
      (fields
        (field (name "MANUFACTURER") "Panasonic")
        (field (name "CASE CODE (IMPERIAL)") "0402")
        (field (name "TOLERANCE") "5%")
        (field (name "RESISTANCE") "0R")
      )
      (libsource (lib "Electronic Devices_LIB") (part "RES_0R_5%_100mW_0402"))
    )
    (comp (ref "R74")
      (value "ERJ-2GE0R00X")
      (footprint "RES_0402_RESC1005X04N")
      (description "SMD Chip Resistor, Jumper, 0 ohm, 100 mW, 0402 [1005 Metric], Thick Film, General Purpose")
      (fields
        (field (name "MANUFACTURER") "Panasonic")
        (field (name "CASE CODE (IMPERIAL)") "0402")
        (field (name "TOLERANCE") "5%")
        (field (name "RESISTANCE") "0R")
      )
      (libsource (lib "Electronic Devices_LIB") (part "RES_0R_5%_100mW_0402"))
    )
    (comp (ref "R75")
      (value "ERJ-2GEJ103X")
      (footprint "RES_0402_RESC1005X04N")
      (description "Res Thick Film 0402 10K Ohm 5% 1/10W ±200ppm/°C Molded SMD Punched Carrier T/R")
      (fields
        (field (name "MANUFACTURER") "Panasonic")
        (field (name "TOLERANCE") "5%")
        (field (name "RESISTANCE") "10K")
        (field (name "CASE/PACKAGE") "0402")
      )
      (libsource (lib "Electronic Devices_LIB") (part "RES_10K_5%_100mW_0402"))
    )
    (comp (ref "R76")
      (value "ERJ-2GE0R00X")
      (footprint "RES_0402_RESC1005X04N")
      (description "SMD Chip Resistor, Jumper, 0 ohm, 100 mW, 0402 [1005 Metric], Thick Film, General Purpose")
      (fields
        (field (name "MANUFACTURER") "Panasonic")
        (field (name "CASE CODE (IMPERIAL)") "0402")
        (field (name "TOLERANCE") "5%")
        (field (name "RESISTANCE") "0R")
      )
      (libsource (lib "Electronic Devices_LIB") (part "RES_0R_5%_100mW_0402"))
    )
    (comp (ref "R77")
      (value "RC0603FR-0740K2L")
      (footprint "RES_0603_RESC1608X04N")
      (description "Res General Purpose Thick Film 0603 40.2K Ohm 1% 1/10W ±100ppm/°C Molded SMD Paper T/R")
      (fields
        (field (name "MANUFACTURER") "Yageo")
        (field (name "TOLERANCE") "1%")
        (field (name "RESISTANCE") "40.2K")
        (field (name "CASE/PACKAGE") "0603")
      )
      (libsource (lib "Electronic Devices_LIB") (part "RES_40.2K_1%_100mW_0603"))
    )
    (comp (ref "SW3")
      (value "PTS645VH83-2LFS")
      (footprint "SW_RA_PTS645VH832LFS")
      (description "Switch Tactile N.O SPST Round Button PC Pins 0.05A 12VDC 100000Cycle 1.96N Thru-Hole Bulk")
      (fields (field (name "MANUFACTURER") "ITT C&K"))
      (libsource (lib "Electronic Devices_LIB") (part "SWITCH_SPST_NO_RA_PTS645VH83-2LFS"))
    )
    (comp (ref "SW4")
      (value "218-2LPSTR")
      (footprint "SW_DIP_2P_2182LPSTR")
      (description "Switch DIP ON OFF SPST 2 Recessed Slide 0.025A 24VDC Gull Wing 1000Cycles 1.27mm SMD T/R")
      (fields (field (name "MANUFACTURER") "CTS"))
      (libsource (lib "Electronic Devices_LIB") (part "SWITCH_DIP_2P_25mA_218-2LPSTR"))
    )
    (comp (ref "SW5")
      (value "218-4LPSTR")
      (footprint "SW_DIP_SOIC127P844X265-8N")
      (description "Switch DIP ON OFF SPST 4 Recessed Slide 0.025A 24VDC Gull Wing 1000Cycles 1.27mm SMD T/R")
      (fields (field (name "MANUFACTURER") "CTS"))
      (libsource (lib "Electronic Devices_LIB") (part "SWITCH_DIP_4P_25mA_218-4LPSTR"))
    )
    (comp (ref "TP5")
      (value "NO COMPONENT")
      (footprint "TP_PAD_1.6MM_SMD_ROUND")
      (description "Test Point, SMD pad, round, 1.5mm, 1.6mm, 3mm diameter")
      (libsource (lib "Electronic Devices_LIB") (part "TP_PAD_SMD_Round"))
    )
    (comp (ref "TP6")
      (value "NO COMPONENT")
      (footprint "TP_PAD_1.6MM_SMD_ROUND")
      (description "Test Point, SMD pad, round, 1.5mm, 1.6mm, 3mm diameter")
      (libsource (lib "Electronic Devices_LIB") (part "TP_PAD_SMD_Round"))
    )
    (comp (ref "U9")
      (value "DS90UB960WRTDRQ1")
      (footprint "IC_DESERIALIZER_QFN50P900X900X90-65N-D")
      (description "Quad 2 MP camera hub FPD-Link III deserializer with dual CSI-2 output ports 64-VQFN -40 to 105")
      (fields (field (name "MANUFACTURER") "Texas Instruments"))
      (libsource (lib "Electronic Devices_LIB") (part "IC_MIPI_DESEREALIZER_DS90UB960WRTDRQ1"))
    )
    (comp (ref "Y4")
      (value "SG-210STF 25.0000ML3")
      (footprint "CRYSTAL_25MHz_SG210STF250000ML3")
      (description "Oscillator XO 25MHz ±50ppm 15pF CMOS 55% 1.8V/2.5V/3.3V Medical 4-Pin SMD T/R")
      (fields (field (name "MANUFACTURER") "Epson"))
      (libsource (lib "Electronic Devices_LIB") (part "CRYSTAL_OSC_25MHz_15pF_SG-210STF 25.0000ML3"))
    )
  )
  (nets
    (net (code "2") (name "/CMLOUT_N") (class "Default")
      (node (ref "C86") (pin "2") (pinfunction "2_2") (pintype "passive"))
      (node (ref "U9") (pin "57") (pinfunction "CMLOUTN_57") (pintype "passive"))
    )
    (net (code "3") (name "/CMLOUT_P") (class "Default")
      (node (ref "C77") (pin "2") (pinfunction "2_2") (pintype "passive"))
      (node (ref "U9") (pin "56") (pinfunction "CMLOUTP_56") (pintype "passive"))
    )
    (net (code "4") (name "/CMLOUT_R_N") (class "Default")
      (node (ref "C86") (pin "1") (pinfunction "1_1") (pintype "passive"))
      (node (ref "R62") (pin "2") (pinfunction "2_2") (pintype "passive"))
      (node (ref "TP6") (pin "1") (pinfunction "1_1") (pintype "passive"))
    )
    (net (code "5") (name "/CMLOUT_R_P") (class "Default")
      (node (ref "C77") (pin "1") (pinfunction "1_1") (pintype "passive"))
      (node (ref "R62") (pin "1") (pinfunction "1_1") (pintype "passive"))
      (node (ref "TP5") (pin "1") (pinfunction "1_1") (pintype "passive"))
    )
    (net (code "6") (name "/CSI0_CLK_N") (class "Default")
      (node (ref "U9") (pin "22") (pinfunction "CSI0_CLKN_22") (pintype "passive"))
    )
    (net (code "7") (name "/CSI0_CLK_P") (class "Default")
      (node (ref "U9") (pin "23") (pinfunction "CSI0_CLKP_23") (pintype "passive"))
    )
    (net (code "8") (name "/CSI0_D0_N") (class "Default")
      (node (ref "U9") (pin "24") (pinfunction "CSI0_D0N_24") (pintype "passive"))
    )
    (net (code "9") (name "/CSI0_D0_P") (class "Default")
      (node (ref "U9") (pin "25") (pinfunction "CSI0_D0P_25") (pintype "passive"))
    )
    (net (code "10") (name "/CSI0_D1_N") (class "Default")
      (node (ref "U9") (pin "26") (pinfunction "CSI0_D1N_26") (pintype "passive"))
    )
    (net (code "11") (name "/CSI0_D1_P") (class "Default")
      (node (ref "U9") (pin "27") (pinfunction "CSI0_D1P_27") (pintype "passive"))
    )
    (net (code "12") (name "/CSI0_D2_N") (class "Default")
      (node (ref "U9") (pin "28") (pinfunction "CSI0_D2N_28") (pintype "passive"))
    )
    (net (code "13") (name "/CSI0_D2_P") (class "Default")
      (node (ref "U9") (pin "29") (pinfunction "CSI0_D2P_29") (pintype "passive"))
    )
    (net (code "14") (name "/CSI0_D3_N") (class "Default")
      (node (ref "U9") (pin "30") (pinfunction "CSI0_D3N_30") (pintype "passive"))
    )
    (net (code "15") (name "/CSI0_D3_P") (class "Default")
      (node (ref "U9") (pin "31") (pinfunction "CSI0_D3P_31") (pintype "passive"))
    )
    (net (code "16") (name "/IDX_DES") (class "Default")
      (node (ref "C109") (pin "2") (pinfunction "2_2") (pintype "passive"))
      (node (ref "J11") (pin "2") (pinfunction "2_2") (pintype "passive"))
      (node (ref "R76") (pin "1") (pinfunction "1_1") (pintype "passive"))
      (node (ref "R77") (pin "2") (pinfunction "2_2") (pintype "passive"))
      (node (ref "U9") (pin "46") (pinfunction "IDX_46") (pintype "passive"))
    )
    (net (code "17") (name "/MODE_DES") (class "Default")
      (node (ref "C102") (pin "2") (pinfunction "2_2") (pintype "passive"))
      (node (ref "SW5") (pin "1") (pinfunction "A1_1") (pintype "passive"))
      (node (ref "SW5") (pin "2") (pinfunction "A2_2") (pintype "passive"))
      (node (ref "SW5") (pin "3") (pinfunction "A3_3") (pintype "passive"))
      (node (ref "SW5") (pin "4") (pinfunction "A4_4") (pintype "passive"))
      (node (ref "U9") (pin "45") (pinfunction "MODE_45") (pintype "passive"))
    )
    (net (code "18") (name "/PDB_DES") (class "Default")
      (node (ref "C93") (pin "2") (pinfunction "2_2") (pintype "passive"))
      (node (ref "R64") (pin "1") (pinfunction "1_1") (pintype "passive"))
      (node (ref "SW3") (pin "2") (pinfunction "NO_2_2") (pintype "passive"))
      (node (ref "SW4") (pin "3") (pinfunction "B2_3") (pintype "passive"))
      (node (ref "U9") (pin "3") (pinfunction "PDB_3") (pintype "passive"))
    )
    (net (code "19") (name "/REFCLK_DES") (class "Default")
      (node (ref "R61") (pin "2") (pinfunction "2_2") (pintype "passive"))
      (node (ref "R74") (pin "2") (pinfunction "2_2") (pintype "passive"))
    )
    (net (code "20") (name "/RIN0_N") (class "Default")
      (node (ref "U9") (pin "51") (pinfunction "RIN0-_51") (pintype "passive"))
    )
    (net (code "21") (name "/RIN0_P") (class "Default")
      (node (ref "U9") (pin "50") (pinfunction "RIN0+_50") (pintype "passive"))
    )
    (net (code "22") (name "/RIN1_N") (class "Default")
      (node (ref "U9") (pin "54") (pinfunction "RIN1-_54") (pintype "passive"))
    )
    (net (code "23") (name "/RIN1_P") (class "Default")
      (node (ref "U9") (pin "53") (pinfunction "RIN1+_53") (pintype "passive"))
    )
    (net (code "24") (name "/SCL_1V8") (class "Default")
      (node (ref "U9") (pin "12") (pinfunction "I2C_SCL_12") (pintype "passive"))
    )
    (net (code "25") (name "/SDA_1V8") (class "Default")
      (node (ref "U9") (pin "11") (pinfunction "I2C_SDA_11") (pintype "passive"))
    )
    (net (code "26") (name "/TESTEN") (class "Default")
      (node (ref "R65") (pin "1") (pinfunction "1_1") (pintype "passive"))
      (node (ref "SW4") (pin "4") (pinfunction "B1_4") (pintype "passive"))
      (node (ref "U9") (pin "4") (pinfunction "RES_4") (pintype "passive"))
    )
    (net (code "28") (name "DCDC_3V3") (class "Default")
      (node (ref "J10") (pin "1") (pinfunction "1_1") (pintype "passive"))
    )
    (net (code "29") (name "GND") (class "Default")
      (node (ref "C100") (pin "1") (pinfunction "1_1") (pintype "passive"))
      (node (ref "C101") (pin "1") (pinfunction "1_1") (pintype "passive"))
      (node (ref "C102") (pin "1") (pinfunction "1_1") (pintype "passive"))
      (node (ref "C103") (pin "1") (pinfunction "1_1") (pintype "passive"))
      (node (ref "C104") (pin "1") (pinfunction "1_1") (pintype "passive"))
      (node (ref "C105") (pin "1") (pinfunction "1_1") (pintype "passive"))
      (node (ref "C106") (pin "1") (pinfunction "1_1") (pintype "passive"))
      (node (ref "C107") (pin "1") (pinfunction "1_1") (pintype "passive"))
      (node (ref "C108") (pin "1") (pinfunction "1_1") (pintype "passive"))
      (node (ref "C109") (pin "1") (pinfunction "1_1") (pintype "passive"))
      (node (ref "C110") (pin "1") (pinfunction "1_1") (pintype "passive"))
      (node (ref "C111") (pin "1") (pinfunction "1_1") (pintype "passive"))
      (node (ref "C112") (pin "1") (pinfunction "1_1") (pintype "passive"))
      (node (ref "C113") (pin "1") (pinfunction "1_1") (pintype "passive"))
      (node (ref "C114") (pin "1") (pinfunction "1_1") (pintype "passive"))
      (node (ref "C64") (pin "1") (pinfunction "1_1") (pintype "passive"))
      (node (ref "C65") (pin "1") (pinfunction "1_1") (pintype "passive"))
      (node (ref "C66") (pin "1") (pinfunction "1_1") (pintype "passive"))
      (node (ref "C67") (pin "1") (pinfunction "1_1") (pintype "passive"))
      (node (ref "C68") (pin "1") (pinfunction "1_1") (pintype "passive"))
      (node (ref "C69") (pin "1") (pinfunction "1_1") (pintype "passive"))
      (node (ref "C70") (pin "1") (pinfunction "1_1") (pintype "passive"))
      (node (ref "C71") (pin "1") (pinfunction "1_1") (pintype "passive"))
      (node (ref "C72") (pin "1") (pinfunction "1_1") (pintype "passive"))
      (node (ref "C73") (pin "1") (pinfunction "1_1") (pintype "passive"))
      (node (ref "C74") (pin "1") (pinfunction "1_1") (pintype "passive"))
      (node (ref "C75") (pin "1") (pinfunction "1_1") (pintype "passive"))
      (node (ref "C76") (pin "1") (pinfunction "1_1") (pintype "passive"))
      (node (ref "C78") (pin "1") (pinfunction "1_1") (pintype "passive"))
      (node (ref "C79") (pin "1") (pinfunction "1_1") (pintype "passive"))
      (node (ref "C80") (pin "1") (pinfunction "1_1") (pintype "passive"))
      (node (ref "C81") (pin "1") (pinfunction "1_1") (pintype "passive"))
      (node (ref "C82") (pin "1") (pinfunction "1_1") (pintype "passive"))
      (node (ref "C83") (pin "1") (pinfunction "1_1") (pintype "passive"))
      (node (ref "C84") (pin "1") (pinfunction "1_1") (pintype "passive"))
      (node (ref "C85") (pin "1") (pinfunction "1_1") (pintype "passive"))
      (node (ref "C87") (pin "1") (pinfunction "1_1") (pintype "passive"))
      (node (ref "C88") (pin "1") (pinfunction "1_1") (pintype "passive"))
      (node (ref "C89") (pin "1") (pinfunction "1_1") (pintype "passive"))
      (node (ref "C90") (pin "1") (pinfunction "1_1") (pintype "passive"))
      (node (ref "C91") (pin "1") (pinfunction "1_1") (pintype "passive"))
      (node (ref "C92") (pin "1") (pinfunction "1_1") (pintype "passive"))
      (node (ref "C93") (pin "1") (pinfunction "1_1") (pintype "passive"))
      (node (ref "C94") (pin "1") (pinfunction "1_1") (pintype "passive"))
      (node (ref "C95") (pin "1") (pinfunction "1_1") (pintype "passive"))
      (node (ref "C96") (pin "1") (pinfunction "1_1") (pintype "passive"))
      (node (ref "C97") (pin "1") (pinfunction "1_1") (pintype "passive"))
      (node (ref "C98") (pin "1") (pinfunction "1_1") (pintype "passive"))
      (node (ref "C99") (pin "1") (pinfunction "1_1") (pintype "passive"))
      (node (ref "R63") (pin "2") (pinfunction "2_2") (pintype "passive"))
      (node (ref "R70") (pin "1") (pinfunction "1_1") (pintype "passive"))
      (node (ref "R71") (pin "1") (pinfunction "1_1") (pintype "passive"))
      (node (ref "R72") (pin "1") (pinfunction "1_1") (pintype "passive"))
      (node (ref "R73") (pin "1") (pinfunction "1_1") (pintype "passive"))
      (node (ref "R77") (pin "1") (pinfunction "1_1") (pintype "passive"))
      (node (ref "SW3") (pin "1") (pinfunction "NO_1_1") (pintype "passive"))
      (node (ref "SW3") (pin "MH1") (pinfunction "MH1_MH1") (pintype "passive"))
      (node (ref "SW3") (pin "MH2") (pinfunction "MH2_MH2") (pintype "passive"))
      (node (ref "SW4") (pin "1") (pinfunction "A1_1") (pintype "passive"))
      (node (ref "SW4") (pin "2") (pinfunction "A2_2") (pintype "passive"))
      (node (ref "U9") (pin "65") (pinfunction "DAP_65") (pintype "passive"))
      (node (ref "Y4") (pin "2") (pinfunction "GND_2") (pintype "passive"))
    )
    (net (code "30") (name "Net-(C110-Pad2)") (class "Default")
      (node (ref "C110") (pin "2") (pinfunction "2_2") (pintype "passive"))
      (node (ref "J10") (pin "2") (pinfunction "2_2") (pintype "passive"))
      (node (ref "L13") (pin "1") (pinfunction "1_1") (pintype "passive"))
    )
    (net (code "31") (name "Net-(SW5-B1)") (class "Default")
      (node (ref "R66") (pin "1") (pinfunction "1_1") (pintype "passive"))
      (node (ref "R70") (pin "2") (pinfunction "2_2") (pintype "passive"))
      (node (ref "SW5") (pin "8") (pinfunction "B1_8") (pintype "passive"))
    )
    (net (code "32") (name "Net-(SW5-B2)") (class "Default")
      (node (ref "R67") (pin "1") (pinfunction "1_1") (pintype "passive"))
      (node (ref "R71") (pin "2") (pinfunction "2_2") (pintype "passive"))
      (node (ref "SW5") (pin "7") (pinfunction "B2_7") (pintype "passive"))
    )
    (net (code "33") (name "Net-(SW5-B3)") (class "Default")
      (node (ref "R68") (pin "1") (pinfunction "1_1") (pintype "passive"))
      (node (ref "R72") (pin "2") (pinfunction "2_2") (pintype "passive"))
      (node (ref "SW5") (pin "6") (pinfunction "B3_6") (pintype "passive"))
    )
    (net (code "34") (name "Net-(SW5-B4)") (class "Default")
      (node (ref "R69") (pin "1") (pinfunction "1_1") (pintype "passive"))
      (node (ref "R73") (pin "2") (pinfunction "2_2") (pintype "passive"))
      (node (ref "SW5") (pin "5") (pinfunction "B4_5") (pintype "passive"))
    )
    (net (code "35") (name "Net-(U9-INTB)") (class "Default")
      (node (ref "R63") (pin "1") (pinfunction "1_1") (pintype "passive"))
      (node (ref "U9") (pin "6") (pinfunction "INTB_6") (pintype "passive"))
    )
    (net (code "36") (name "Net-(U9-REFCLK)") (class "Default")
      (node (ref "R61") (pin "1") (pinfunction "1_1") (pintype "passive"))
      (node (ref "U9") (pin "5") (pinfunction "REFCLK_5") (pintype "passive"))
    )
    (net (code "37") (name "Net-(Y4-OUT)") (class "Default")
      (node (ref "R74") (pin "1") (pinfunction "1_1") (pintype "passive"))
      (node (ref "Y4") (pin "3") (pinfunction "OUT_3") (pintype "passive"))
    )
    (net (code "38") (name "Net-(Y4-~{ST})") (class "Default")
      (node (ref "R75") (pin "2") (pinfunction "2_2") (pintype "passive"))
      (node (ref "Y4") (pin "1") (pinfunction "~{ST}_1") (pintype "passive"))
    )
    (net (code "39") (name "VDD18A") (class "Default")
      (node (ref "C65") (pin "2") (pinfunction "2_2") (pintype "passive"))
      (node (ref "C66") (pin "2") (pinfunction "2_2") (pintype "passive"))
      (node (ref "C67") (pin "2") (pinfunction "2_2") (pintype "passive"))
      (node (ref "C68") (pin "2") (pinfunction "2_2") (pintype "passive"))
      (node (ref "L7") (pin "2") (pinfunction "2_2") (pintype "passive"))
      (node (ref "U9") (pin "32") (pinfunction "VDD18A_32") (pintype "passive"))
    )
    (net (code "40") (name "VDD18_P") (class "Default")
      (node (ref "C79") (pin "2") (pinfunction "2_2") (pintype "passive"))
      (node (ref "C80") (pin "2") (pinfunction "2_2") (pintype "passive"))
      (node (ref "C81") (pin "2") (pinfunction "2_2") (pintype "passive"))
      (node (ref "C82") (pin "2") (pinfunction "2_2") (pintype "passive"))
      (node (ref "C83") (pin "2") (pinfunction "2_2") (pintype "passive"))
      (node (ref "C84") (pin "2") (pinfunction "2_2") (pintype "passive"))
      (node (ref "C85") (pin "2") (pinfunction "2_2") (pintype "passive"))
      (node (ref "L9") (pin "2") (pinfunction "2_2") (pintype "passive"))
      (node (ref "U9") (pin "1") (pinfunction "VDD18_P3_1") (pintype "passive"))
      (node (ref "U9") (pin "2") (pinfunction "VDD18_P2_2") (pintype "passive"))
      (node (ref "U9") (pin "47") (pinfunction "VDD18_P1_47") (pintype "passive"))
      (node (ref "U9") (pin "48") (pinfunction "VDD18_P0_48") (pintype "passive"))
    )
    (net (code "41") (name "VDDCSI_1V1") (class "Default")
      (node (ref "C95") (pin "2") (pinfunction "2_2") (pintype "passive"))
      (node (ref "C96") (pin "2") (pinfunction "2_2") (pintype "passive"))
      (node (ref "C97") (pin "2") (pinfunction "2_2") (pintype "passive"))
      (node (ref "C98") (pin "2") (pinfunction "2_2") (pintype "passive"))
      (node (ref "C99") (pin "2") (pinfunction "2_2") (pintype "passive"))
      (node (ref "L11") (pin "2") (pinfunction "2_2") (pintype "passive"))
      (node (ref "U9") (pin "21") (pinfunction "VDD_CSI0_21") (pintype "passive"))
      (node (ref "U9") (pin "33") (pinfunction "VDD_CSI1_33") (pintype "passive"))
    )
    (net (code "42") (name "VDDFPD18") (class "Default")
      (node (ref "C70") (pin "2") (pinfunction "2_2") (pintype "passive"))
      (node (ref "C71") (pin "2") (pinfunction "2_2") (pintype "passive"))
      (node (ref "C72") (pin "2") (pinfunction "2_2") (pintype "passive"))
      (node (ref "C73") (pin "2") (pinfunction "2_2") (pintype "passive"))
      (node (ref "C74") (pin "2") (pinfunction "2_2") (pintype "passive"))
      (node (ref "C75") (pin "2") (pinfunction "2_2") (pintype "passive"))
      (node (ref "C76") (pin "2") (pinfunction "2_2") (pintype "passive"))
      (node (ref "L8") (pin "2") (pinfunction "2_2") (pintype "passive"))
      (node (ref "U9") (pin "49") (pinfunction "VDD18_FPD0_49") (pintype "passive"))
      (node (ref "U9") (pin "55") (pinfunction "VDD18_FPD1_55") (pintype "passive"))
      (node (ref "U9") (pin "58") (pinfunction "VDD18_FPD2_58") (pintype "passive"))
      (node (ref "U9") (pin "64") (pinfunction "VDD18_FPD3_64") (pintype "passive"))
    )
    (net (code "43") (name "VDDFPD_1V1") (class "Default")
      (node (ref "C104") (pin "2") (pinfunction "2_2") (pintype "passive"))
      (node (ref "C105") (pin "2") (pinfunction "2_2") (pintype "passive"))
      (node (ref "C106") (pin "2") (pinfunction "2_2") (pintype "passive"))
      (node (ref "C107") (pin "2") (pinfunction "2_2") (pintype "passive"))
      (node (ref "C108") (pin "2") (pinfunction "2_2") (pintype "passive"))
      (node (ref "L12") (pin "2") (pinfunction "2_2") (pintype "passive"))
      (node (ref "U9") (pin "52") (pinfunction "VDD_FPD1_52") (pintype "passive"))
      (node (ref "U9") (pin "61") (pinfunction "VDD_FPD2_61") (pintype "passive"))
    )
    (net (code "44") (name "VDDIO") (class "Default")
      (node (ref "C100") (pin "2") (pinfunction "2_2") (pintype "passive"))
      (node (ref "C101") (pin "2") (pinfunction "2_2") (pintype "passive"))
      (node (ref "C111") (pin "2") (pinfunction "2_2") (pintype "passive"))
      (node (ref "C112") (pin "2") (pinfunction "2_2") (pintype "passive"))
      (node (ref "C113") (pin "2") (pinfunction "2_2") (pintype "passive"))
      (node (ref "C114") (pin "2") (pinfunction "2_2") (pintype "passive"))
      (node (ref "L13") (pin "2") (pinfunction "2_2") (pintype "passive"))
      (node (ref "R65") (pin "2") (pinfunction "2_2") (pintype "passive"))
      (node (ref "R75") (pin "1") (pinfunction "1_1") (pintype "passive"))
      (node (ref "U9") (pin "16") (pinfunction "VDDIO_16") (pintype "passive"))
      (node (ref "Y4") (pin "4") (pinfunction "VCC_4") (pintype "passive"))
    )
    (net (code "45") (name "VDDL_1V1") (class "Default")
      (node (ref "C88") (pin "2") (pinfunction "2_2") (pintype "passive"))
      (node (ref "C89") (pin "2") (pinfunction "2_2") (pintype "passive"))
      (node (ref "C90") (pin "2") (pinfunction "2_2") (pintype "passive"))
      (node (ref "C91") (pin "2") (pinfunction "2_2") (pintype "passive"))
      (node (ref "C92") (pin "2") (pinfunction "2_2") (pintype "passive"))
      (node (ref "L10") (pin "2") (pinfunction "2_2") (pintype "passive"))
      (node (ref "U9") (pin "13") (pinfunction "VDDL1_13") (pintype "passive"))
      (node (ref "U9") (pin "44") (pinfunction "VDDL2_44") (pintype "passive"))
    )
    (net (code "46") (name "VDD_1V1") (class "Default")
      (node (ref "C103") (pin "2") (pinfunction "2_2") (pintype "passive"))
      (node (ref "C87") (pin "2") (pinfunction "2_2") (pintype "passive"))
      (node (ref "C94") (pin "2") (pinfunction "2_2") (pintype "passive"))
      (node (ref "L10") (pin "1") (pinfunction "1_1") (pintype "passive"))
      (node (ref "L11") (pin "1") (pinfunction "1_1") (pintype "passive"))
      (node (ref "L12") (pin "1") (pinfunction "1_1") (pintype "passive"))
    )
    (net (code "47") (name "VDD_1V8_DES") (class "Default")
      (node (ref "C64") (pin "2") (pinfunction "2_2") (pintype "passive"))
      (node (ref "C69") (pin "2") (pinfunction "2_2") (pintype "passive"))
      (node (ref "C78") (pin "2") (pinfunction "2_2") (pintype "passive"))
      (node (ref "J10") (pin "3") (pinfunction "3_3") (pintype "passive"))
      (node (ref "J11") (pin "1") (pinfunction "1_1") (pintype "passive"))
      (node (ref "L7") (pin "1") (pinfunction "1_1") (pintype "passive"))
      (node (ref "L8") (pin "1") (pinfunction "1_1") (pintype "passive"))
      (node (ref "L9") (pin "1") (pinfunction "1_1") (pintype "passive"))
      (node (ref "R64") (pin "2") (pinfunction "2_2") (pintype "passive"))
      (node (ref "R66") (pin "2") (pinfunction "2_2") (pintype "passive"))
      (node (ref "R67") (pin "2") (pinfunction "2_2") (pintype "passive"))
      (node (ref "R68") (pin "2") (pinfunction "2_2") (pintype "passive"))
      (node (ref "R69") (pin "2") (pinfunction "2_2") (pintype "passive"))
      (node (ref "R76") (pin "2") (pinfunction "2_2") (pintype "passive"))
    )
    (net (code "48") (name "unconnected-(U9-CSI1_CLKN-Pad34)") (class "Default")
      (node (ref "U9") (pin "34") (pinfunction "CSI1_CLKN_34") (pintype "passive+no_connect"))
    )
    (net (code "49") (name "unconnected-(U9-CSI1_CLKP-Pad35)") (class "Default")
      (node (ref "U9") (pin "35") (pinfunction "CSI1_CLKP_35") (pintype "passive+no_connect"))
    )
    (net (code "50") (name "unconnected-(U9-CSI1_D0N-Pad36)") (class "Default")
      (node (ref "U9") (pin "36") (pinfunction "CSI1_D0N_36") (pintype "passive+no_connect"))
    )
    (net (code "51") (name "unconnected-(U9-CSI1_D0P-Pad37)") (class "Default")
      (node (ref "U9") (pin "37") (pinfunction "CSI1_D0P_37") (pintype "passive+no_connect"))
    )
    (net (code "52") (name "unconnected-(U9-CSI1_D1N-Pad38)") (class "Default")
      (node (ref "U9") (pin "38") (pinfunction "CSI1_D1N_38") (pintype "passive+no_connect"))
    )
    (net (code "53") (name "unconnected-(U9-CSI1_D1P-Pad39)") (class "Default")
      (node (ref "U9") (pin "39") (pinfunction "CSI1_D1P_39") (pintype "passive+no_connect"))
    )
    (net (code "54") (name "unconnected-(U9-CSI1_D2N-Pad40)") (class "Default")
      (node (ref "U9") (pin "40") (pinfunction "CSI1_D2N_40") (pintype "passive+no_connect"))
    )
    (net (code "55") (name "unconnected-(U9-CSI1_D2P-Pad41)") (class "Default")
      (node (ref "U9") (pin "41") (pinfunction "CSI1_D2P_41") (pintype "passive+no_connect"))
    )
    (net (code "56") (name "unconnected-(U9-CSI1_D3N-Pad42)") (class "Default")
      (node (ref "U9") (pin "42") (pinfunction "CSI1_D3N_42") (pintype "passive+no_connect"))
    )
    (net (code "57") (name "unconnected-(U9-CSI1_D3P-Pad43)") (class "Default")
      (node (ref "U9") (pin "43") (pinfunction "CSI1_D3P_43") (pintype "passive+no_connect"))
    )
    (net (code "58") (name "unconnected-(U9-GPIO0-Pad9)") (class "Default")
      (node (ref "U9") (pin "9") (pinfunction "GPIO0_9") (pintype "passive+no_connect"))
    )
    (net (code "59") (name "unconnected-(U9-GPIO1-Pad10)") (class "Default")
      (node (ref "U9") (pin "10") (pinfunction "GPIO1_10") (pintype "passive+no_connect"))
    )
    (net (code "60") (name "unconnected-(U9-GPIO2-Pad14)") (class "Default")
      (node (ref "U9") (pin "14") (pinfunction "GPIO2_14") (pintype "passive+no_connect"))
    )
    (net (code "61") (name "unconnected-(U9-GPIO3-Pad15)") (class "Default")
      (node (ref "U9") (pin "15") (pinfunction "GPIO3_15") (pintype "passive+no_connect"))
    )
    (net (code "62") (name "unconnected-(U9-GPIO4-Pad17)") (class "Default")
      (node (ref "U9") (pin "17") (pinfunction "GPIO4_17") (pintype "passive+no_connect"))
    )
    (net (code "63") (name "unconnected-(U9-GPIO5-Pad18)") (class "Default")
      (node (ref "U9") (pin "18") (pinfunction "GPIO5_18") (pintype "passive+no_connect"))
    )
    (net (code "64") (name "unconnected-(U9-GPIO6-Pad19)") (class "Default")
      (node (ref "U9") (pin "19") (pinfunction "GPIO6_19") (pintype "passive+no_connect"))
    )
    (net (code "65") (name "unconnected-(U9-GPIO7-Pad20)") (class "Default")
      (node (ref "U9") (pin "20") (pinfunction "GPIO7_20") (pintype "passive+no_connect"))
    )
    (net (code "66") (name "unconnected-(U9-I2C_SCL2-Pad8)") (class "Default")
      (node (ref "U9") (pin "8") (pinfunction "I2C_SCL2_8") (pintype "passive+no_connect"))
    )
    (net (code "67") (name "unconnected-(U9-I2C_SDA2-Pad7)") (class "Default")
      (node (ref "U9") (pin "7") (pinfunction "I2C_SDA2_7") (pintype "passive+no_connect"))
    )
    (net (code "68") (name "unconnected-(U9-RIN2+-Pad59)") (class "Default")
      (node (ref "U9") (pin "59") (pinfunction "RIN2+_59") (pintype "passive+no_connect"))
    )
    (net (code "69") (name "unconnected-(U9-RIN2--Pad60)") (class "Default")
      (node (ref "U9") (pin "60") (pinfunction "RIN2-_60") (pintype "passive+no_connect"))
    )
    (net (code "70") (name "unconnected-(U9-RIN3+-Pad62)") (class "Default")
      (node (ref "U9") (pin "62") (pinfunction "RIN3+_62") (pintype "passive+no_connect"))
    )
    (net (code "71") (name "unconnected-(U9-RIN3--Pad63)") (class "Default")
      (node (ref "U9") (pin "63") (pinfunction "RIN3-_63") (pintype "passive+no_connect"))
    )
  )
)
